# 5v-switch-sensor.net
KiCad netlist of a schematic drawn in EAGLE
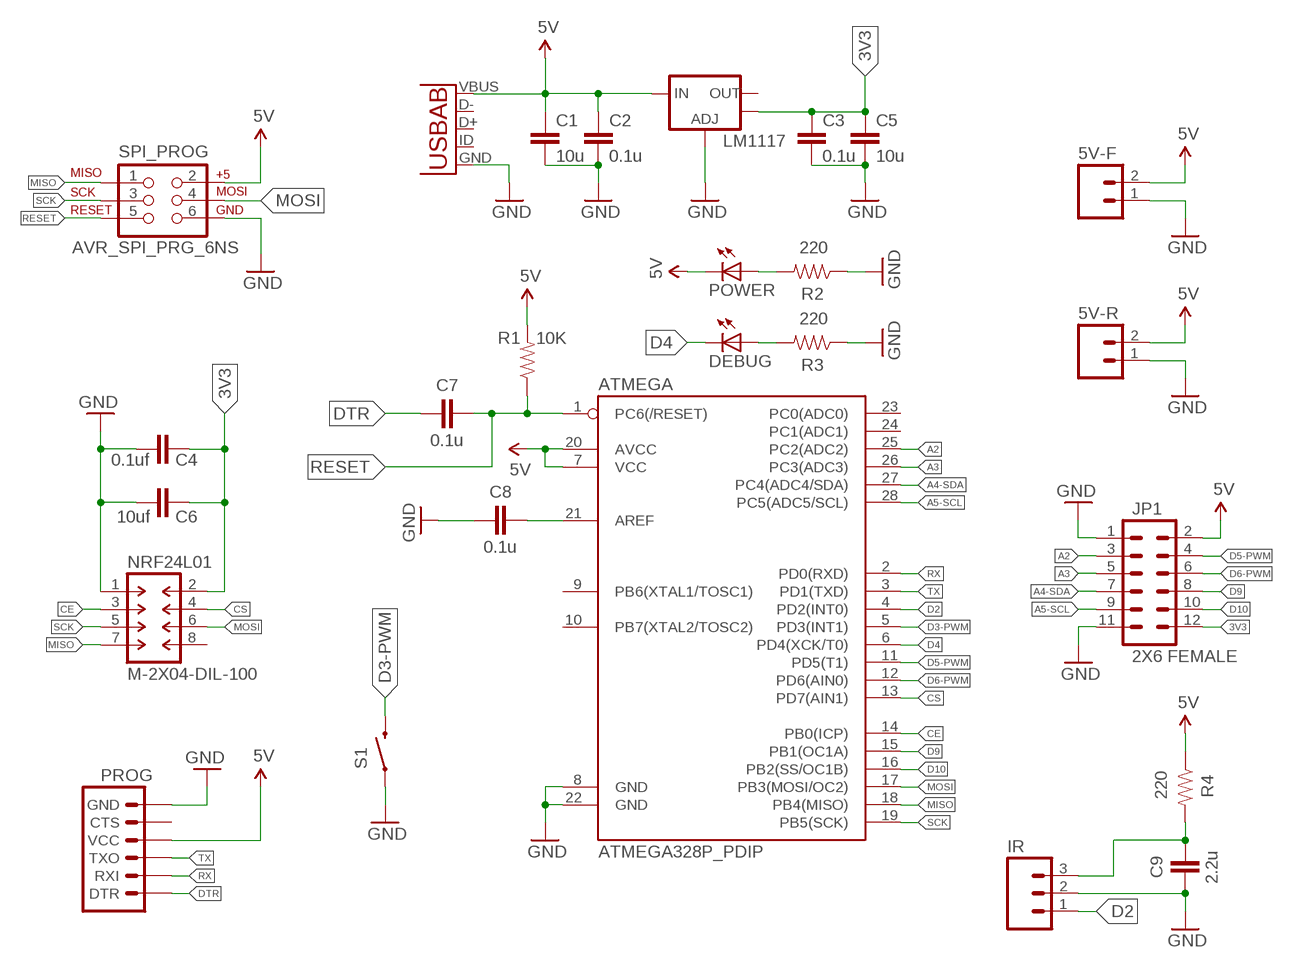
[diagram p0: schematic, sheet 1]

(export (version "E")
  (design (tool "Eeschema 10.0.6"))
  (components
    (comp (ref "5V-F")
      (value "M02PTH")
      (footprint "eagle-import:1X02")
      (libsource (lib "eagle-import") (part "M02PTH"))
    )
    (comp (ref "5V-R")
      (value "M02PTH")
      (footprint "eagle-import:1X02")
      (libsource (lib "eagle-import") (part "M02PTH"))
    )
    (comp (ref "ATMEGA")
      (value "ATMEGA328P_PDIP")
      (footprint "eagle-import:DIL28-3")
      (libsource (lib "eagle-import") (part "ATMEGA328P_PDIP"))
    )
    (comp (ref "C1")
      (value "10u")
      (footprint "eagle-import:0805")
      (libsource (lib "eagle-import") (part "CAP0805"))
    )
    (comp (ref "C2")
      (value "0.1u")
      (footprint "eagle-import:0805")
      (libsource (lib "eagle-import") (part "CAP0805"))
    )
    (comp (ref "C3")
      (value "0.1u")
      (footprint "eagle-import:0805")
      (libsource (lib "eagle-import") (part "CAP0805"))
    )
    (comp (ref "C4")
      (value "0.1uf")
      (footprint "eagle-import:0805")
      (libsource (lib "eagle-import") (part "CAP0805"))
    )
    (comp (ref "C5")
      (value "10u")
      (footprint "eagle-import:0805")
      (libsource (lib "eagle-import") (part "CAP0805"))
    )
    (comp (ref "C6")
      (value "10uf")
      (footprint "eagle-import:0805")
      (libsource (lib "eagle-import") (part "CAP0805"))
    )
    (comp (ref "C7")
      (value "0.1u")
      (footprint "eagle-import:0805")
      (libsource (lib "eagle-import") (part "CAP0805"))
    )
    (comp (ref "C8")
      (value "0.1u")
      (footprint "eagle-import:0805")
      (libsource (lib "eagle-import") (part "CAP0805"))
    )
    (comp (ref "C9")
      (value "2.2u")
      (footprint "eagle-import:0805")
      (libsource (lib "eagle-import") (part "CAP0805"))
    )
    (comp (ref "DEBUG")
      (value "LEDCHIPLED_0805")
      (footprint "eagle-import:CHIPLED_0805")
      (libsource (lib "eagle-import") (part "LEDCHIPLED_0805"))
    )
    (comp (ref "IR")
      (value "M03PTH")
      (footprint "eagle-import:1X03")
      (libsource (lib "eagle-import") (part "M03PTH"))
    )
    (comp (ref "JP1")
      (value "2X6 FEMALE")
      (footprint "eagle-import:2X6")
      (libsource (lib "eagle-import") (part "M06X2PTH_FEMALE"))
    )
    (comp (ref "LM1117")
      (value "V_REG_LM1117SOT223")
      (footprint "eagle-import:SOT223")
      (libsource (lib "eagle-import") (part "V_REG_LM1117SOT223"))
    )
    (comp (ref "NRF24L01")
      (value "M-2X04-DIL-100")
      (footprint "eagle-import:DIL-100-2X04")
      (libsource (lib "eagle-import") (part "M-2X04-DIL-100"))
    )
    (comp (ref "POWER")
      (value "LEDCHIPLED_0805")
      (footprint "eagle-import:CHIPLED_0805")
      (libsource (lib "eagle-import") (part "LEDCHIPLED_0805"))
    )
    (comp (ref "PROG")
      (value "ARDUINO_SERIAL_PROGRAMPTH")
      (footprint "eagle-import:1X06")
      (libsource (lib "eagle-import") (part "ARDUINO_SERIAL_PROGRAMPTH"))
    )
    (comp (ref "R1")
      (value "10K")
      (footprint "eagle-import:0805")
      (libsource (lib "eagle-import") (part "RESISTOR0805-RES"))
    )
    (comp (ref "R2")
      (value "220")
      (footprint "eagle-import:0805")
      (libsource (lib "eagle-import") (part "RESISTOR0805-RES"))
    )
    (comp (ref "R3")
      (value "220")
      (footprint "eagle-import:0805")
      (libsource (lib "eagle-import") (part "RESISTOR0805-RES"))
    )
    (comp (ref "R4")
      (value "220")
      (footprint "eagle-import:0805")
      (libsource (lib "eagle-import") (part "RESISTOR0805-RES"))
    )
    (comp (ref "S1")
      (value "SWITCH-MOMENTARY-2SMD-1101NE")
      (footprint "eagle-import:TACTILE-SWITCH-1101NE")
      (libsource (lib "eagle-import") (part "SWITCH-MOMENTARY-2SMD-1101NE"))
    )
    (comp (ref "SPI_PROG")
      (value "AVR_SPI_PRG_6NS")
      (footprint "eagle-import:2X3-NS")
      (libsource (lib "eagle-import") (part "AVR_SPI_PRG_6NS"))
    )
    (comp (ref "U1")
      (value "USB-AB")
      (footprint "eagle-import:USB-AB-MICRO-SMD")
      (libsource (lib "eagle-import") (part "USB-AB"))
    )
  )
  (nets
    (net (code "1") (name "3V3") (class "Default")
      (node (ref "C3") (pin "1") (pinfunction "1_1") (pintype "passive"))
      (node (ref "C4") (pin "1") (pinfunction "1_1") (pintype "passive"))
      (node (ref "C5") (pin "1") (pinfunction "1_1") (pintype "passive"))
      (node (ref "C6") (pin "1") (pinfunction "1_1") (pintype "passive"))
      (node (ref "JP1") (pin "12") (pinfunction "12_12") (pintype "passive"))
      (node (ref "LM1117") (pin "4") (pinfunction "OUT_4") (pintype "output"))
      (node (ref "NRF24L01") (pin "2") (pinfunction "2_2") (pintype "passive"))
    )
    (net (code "2") (name "5V") (class "Default")
      (node (ref "5V-F") (pin "2") (pinfunction "2_2") (pintype "passive"))
      (node (ref "5V-R") (pin "2") (pinfunction "2_2") (pintype "passive"))
      (node (ref "ATMEGA") (pin "20") (pinfunction "AVCC_20") (pintype "bidirectional"))
      (node (ref "ATMEGA") (pin "7") (pinfunction "VCC_7") (pintype "bidirectional"))
      (node (ref "C1") (pin "1") (pinfunction "1_1") (pintype "passive"))
      (node (ref "C2") (pin "1") (pinfunction "1_1") (pintype "passive"))
      (node (ref "JP1") (pin "2") (pinfunction "2_2") (pintype "passive"))
      (node (ref "LM1117") (pin "3") (pinfunction "IN_3") (pintype "input"))
      (node (ref "POWER") (pin "C") (pinfunction "C_C") (pintype "passive"))
      (node (ref "PROG") (pin "4") (pinfunction "VCC_4") (pintype "passive"))
      (node (ref "R1") (pin "2") (pinfunction "2_2") (pintype "passive"))
      (node (ref "R4") (pin "1") (pinfunction "1_1") (pintype "passive"))
      (node (ref "SPI_PROG") (pin "2") (pinfunction "2_2") (pintype "passive"))
      (node (ref "U1") (pin "VBUS") (pinfunction "VBUS_VBUS") (pintype "bidirectional"))
    )
    (net (code "3") (name "A2") (class "Default")
      (node (ref "ATMEGA") (pin "25") (pinfunction "PC2(ADC2)_25") (pintype "bidirectional"))
      (node (ref "JP1") (pin "3") (pinfunction "3_3") (pintype "passive"))
    )
    (net (code "4") (name "A3") (class "Default")
      (node (ref "ATMEGA") (pin "26") (pinfunction "PC3(ADC3)_26") (pintype "bidirectional"))
      (node (ref "JP1") (pin "5") (pinfunction "5_5") (pintype "passive"))
    )
    (net (code "5") (name "A4-SDA") (class "Default")
      (node (ref "ATMEGA") (pin "27") (pinfunction "PC4(ADC4/SDA)_27") (pintype "bidirectional"))
      (node (ref "JP1") (pin "7") (pinfunction "7_7") (pintype "passive"))
    )
    (net (code "6") (name "A5-SCL") (class "Default")
      (node (ref "ATMEGA") (pin "28") (pinfunction "PC5(ADC5/SCL)_28") (pintype "bidirectional"))
      (node (ref "JP1") (pin "9") (pinfunction "9_9") (pintype "passive"))
    )
    (net (code "7") (name "CE") (class "Default")
      (node (ref "ATMEGA") (pin "14") (pinfunction "PB0(ICP)_14") (pintype "bidirectional"))
      (node (ref "NRF24L01") (pin "3") (pinfunction "3_3") (pintype "passive"))
    )
    (net (code "8") (name "CS") (class "Default")
      (node (ref "ATMEGA") (pin "13") (pinfunction "PD7(AIN1)_13") (pintype "bidirectional"))
      (node (ref "NRF24L01") (pin "4") (pinfunction "4_4") (pintype "passive"))
    )
    (net (code "9") (name "D2") (class "Default")
      (node (ref "ATMEGA") (pin "4") (pinfunction "PD2(INT0)_4") (pintype "bidirectional"))
      (node (ref "IR") (pin "1") (pinfunction "1_1") (pintype "passive"))
    )
    (net (code "10") (name "D3-PWM") (class "Default")
      (node (ref "ATMEGA") (pin "5") (pinfunction "PD3(INT1)_5") (pintype "bidirectional"))
      (node (ref "S1") (pin "2") (pinfunction "2_2") (pintype "passive"))
    )
    (net (code "11") (name "D4") (class "Default")
      (node (ref "ATMEGA") (pin "6") (pinfunction "PD4(XCK/T0)_6") (pintype "bidirectional"))
      (node (ref "DEBUG") (pin "C") (pinfunction "C_C") (pintype "passive"))
    )
    (net (code "12") (name "D5-PWM") (class "Default")
      (node (ref "ATMEGA") (pin "11") (pinfunction "PD5(T1)_11") (pintype "bidirectional"))
      (node (ref "JP1") (pin "4") (pinfunction "4_4") (pintype "passive"))
    )
    (net (code "13") (name "D6-PWM") (class "Default")
      (node (ref "ATMEGA") (pin "12") (pinfunction "PD6(AIN0)_12") (pintype "bidirectional"))
      (node (ref "JP1") (pin "6") (pinfunction "6_6") (pintype "passive"))
    )
    (net (code "14") (name "D9") (class "Default")
      (node (ref "ATMEGA") (pin "15") (pinfunction "PB1(OC1A)_15") (pintype "bidirectional"))
      (node (ref "JP1") (pin "8") (pinfunction "8_8") (pintype "passive"))
    )
    (net (code "15") (name "D10") (class "Default")
      (node (ref "ATMEGA") (pin "16") (pinfunction "PB2(SS/OC1B)_16") (pintype "bidirectional"))
      (node (ref "JP1") (pin "10") (pinfunction "10_10") (pintype "passive"))
    )
    (net (code "16") (name "DTR") (class "Default")
      (node (ref "C7") (pin "1") (pinfunction "1_1") (pintype "passive"))
      (node (ref "PROG") (pin "1") (pinfunction "DTR_1") (pintype "passive"))
    )
    (net (code "17") (name "GND") (class "Default")
      (node (ref "5V-F") (pin "1") (pinfunction "1_1") (pintype "passive"))
      (node (ref "5V-R") (pin "1") (pinfunction "1_1") (pintype "passive"))
      (node (ref "ATMEGA") (pin "22") (pinfunction "GND_22") (pintype "bidirectional"))
      (node (ref "ATMEGA") (pin "8") (pinfunction "GND_8") (pintype "bidirectional"))
      (node (ref "C1") (pin "2") (pinfunction "2_2") (pintype "passive"))
      (node (ref "C2") (pin "2") (pinfunction "2_2") (pintype "passive"))
      (node (ref "C3") (pin "2") (pinfunction "2_2") (pintype "passive"))
      (node (ref "C4") (pin "2") (pinfunction "2_2") (pintype "passive"))
      (node (ref "C5") (pin "2") (pinfunction "2_2") (pintype "passive"))
      (node (ref "C6") (pin "2") (pinfunction "2_2") (pintype "passive"))
      (node (ref "C8") (pin "1") (pinfunction "1_1") (pintype "passive"))
      (node (ref "C9") (pin "1") (pinfunction "1_1") (pintype "passive"))
      (node (ref "IR") (pin "2") (pinfunction "2_2") (pintype "passive"))
      (node (ref "JP1") (pin "1") (pinfunction "1_1") (pintype "passive"))
      (node (ref "JP1") (pin "11") (pinfunction "11_11") (pintype "passive"))
      (node (ref "LM1117") (pin "1") (pinfunction "ADJ_1") (pintype "input"))
      (node (ref "NRF24L01") (pin "1") (pinfunction "1_1") (pintype "passive"))
      (node (ref "PROG") (pin "6") (pinfunction "GND_6") (pintype "passive"))
      (node (ref "R2") (pin "1") (pinfunction "1_1") (pintype "passive"))
      (node (ref "R3") (pin "1") (pinfunction "1_1") (pintype "passive"))
      (node (ref "S1") (pin "1") (pinfunction "1_1") (pintype "passive"))
      (node (ref "SPI_PROG") (pin "6") (pinfunction "6_6") (pintype "passive"))
      (node (ref "U1") (pin "GND") (pinfunction "GND_GND") (pintype "bidirectional"))
    )
    (net (code "18") (name "MISO") (class "Default")
      (node (ref "ATMEGA") (pin "18") (pinfunction "PB4(MISO)_18") (pintype "bidirectional"))
      (node (ref "NRF24L01") (pin "7") (pinfunction "7_7") (pintype "passive"))
      (node (ref "SPI_PROG") (pin "1") (pinfunction "1_1") (pintype "passive"))
    )
    (net (code "19") (name "MOSI") (class "Default")
      (node (ref "ATMEGA") (pin "17") (pinfunction "PB3(MOSI/OC2)_17") (pintype "bidirectional"))
      (node (ref "NRF24L01") (pin "6") (pinfunction "6_6") (pintype "passive"))
      (node (ref "SPI_PROG") (pin "4") (pinfunction "4_4") (pintype "passive"))
    )
    (net (code "20") (name "Net-(ATMEGA-AREF)") (class "Default")
      (node (ref "ATMEGA") (pin "21") (pinfunction "AREF_21") (pintype "bidirectional"))
      (node (ref "C8") (pin "2") (pinfunction "2_2") (pintype "passive"))
    )
    (net (code "21") (name "Net-(C9-Pad2)") (class "Default")
      (node (ref "C9") (pin "2") (pinfunction "2_2") (pintype "passive"))
      (node (ref "IR") (pin "3") (pinfunction "3_3") (pintype "passive"))
      (node (ref "R4") (pin "2") (pinfunction "2_2") (pintype "passive"))
    )
    (net (code "22") (name "Net-(DEBUG-PadA)") (class "Default")
      (node (ref "DEBUG") (pin "A") (pinfunction "A_A") (pintype "passive"))
      (node (ref "R3") (pin "2") (pinfunction "2_2") (pintype "passive"))
    )
    (net (code "23") (name "Net-(POWER-PadA)") (class "Default")
      (node (ref "POWER") (pin "A") (pinfunction "A_A") (pintype "passive"))
      (node (ref "R2") (pin "2") (pinfunction "2_2") (pintype "passive"))
    )
    (net (code "24") (name "RESET") (class "Default")
      (node (ref "ATMEGA") (pin "1") (pinfunction "PC6(/RESET)_1") (pintype "bidirectional"))
      (node (ref "C7") (pin "2") (pinfunction "2_2") (pintype "passive"))
      (node (ref "R1") (pin "1") (pinfunction "1_1") (pintype "passive"))
      (node (ref "SPI_PROG") (pin "5") (pinfunction "5_5") (pintype "passive"))
    )
    (net (code "25") (name "RX") (class "Default")
      (node (ref "ATMEGA") (pin "2") (pinfunction "PD0(RXD)_2") (pintype "bidirectional"))
      (node (ref "PROG") (pin "2") (pinfunction "RXI_2") (pintype "passive"))
    )
    (net (code "26") (name "SCK") (class "Default")
      (node (ref "ATMEGA") (pin "19") (pinfunction "PB5(SCK)_19") (pintype "bidirectional"))
      (node (ref "NRF24L01") (pin "5") (pinfunction "5_5") (pintype "passive"))
      (node (ref "SPI_PROG") (pin "3") (pinfunction "3_3") (pintype "passive"))
    )
    (net (code "27") (name "TX") (class "Default")
      (node (ref "ATMEGA") (pin "3") (pinfunction "PD1(TXD)_3") (pintype "bidirectional"))
      (node (ref "PROG") (pin "3") (pinfunction "TXO_3") (pintype "passive"))
    )
    (net (code "28") (name "unconnected-(ATMEGA-PB6(XTAL1{slash}TOSC1)-Pad9)") (class "Default")
      (node (ref "ATMEGA") (pin "9") (pinfunction "PB6(XTAL1/TOSC1)_9") (pintype "bidirectional"))
    )
    (net (code "29") (name "unconnected-(ATMEGA-PB7(XTAL2{slash}TOSC2)-Pad10)") (class "Default")
      (node (ref "ATMEGA") (pin "10") (pinfunction "PB7(XTAL2/TOSC2)_10") (pintype "bidirectional"))
    )
    (net (code "30") (name "unconnected-(ATMEGA-PC0(ADC0)-Pad23)") (class "Default")
      (node (ref "ATMEGA") (pin "23") (pinfunction "PC0(ADC0)_23") (pintype "bidirectional"))
    )
    (net (code "31") (name "unconnected-(ATMEGA-PC1(ADC1)-Pad24)") (class "Default")
      (node (ref "ATMEGA") (pin "24") (pinfunction "PC1(ADC1)_24") (pintype "bidirectional"))
    )
    (net (code "32") (name "unconnected-(LM1117-OUT-Pad2)") (class "Default")
      (node (ref "LM1117") (pin "2") (pinfunction "OUT_2") (pintype "output"))
    )
    (net (code "33") (name "unconnected-(NRF24L01-Pad8)") (class "Default")
      (node (ref "NRF24L01") (pin "8") (pinfunction "8_8") (pintype "passive"))
    )
    (net (code "34") (name "unconnected-(PROG-CTS-Pad5)") (class "Default")
      (node (ref "PROG") (pin "5") (pinfunction "CTS_5") (pintype "passive"))
    )
    (net (code "35") (name "unconnected-(U1-PadD+)") (class "Default")
      (node (ref "U1") (pin "D+") (pinfunction "D+_D+") (pintype "bidirectional"))
    )
    (net (code "36") (name "unconnected-(U1-PadD-)") (class "Default")
      (node (ref "U1") (pin "D-") (pinfunction "D-_D-") (pintype "bidirectional"))
    )
    (net (code "37") (name "unconnected-(U1-USBID-PadID)") (class "Default")
      (node (ref "U1") (pin "ID") (pinfunction "USBID_ID") (pintype "bidirectional"))
    )
  )
)
